# oled.net
KiCad netlist of a schematic drawn in Altium Designer
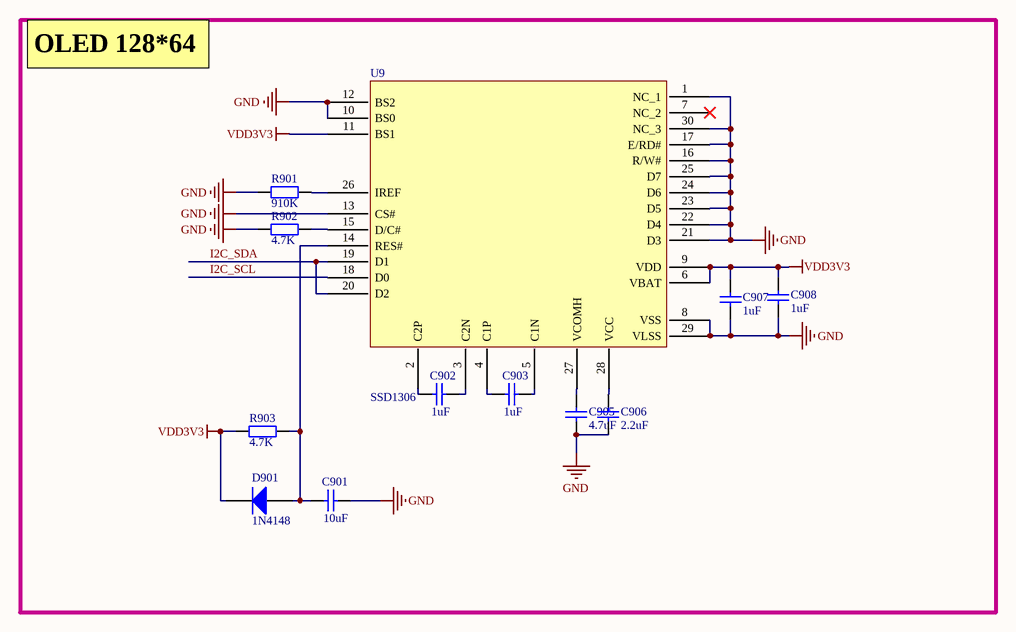
[diagram p0: oled.SchDoc]

(export (version "E")
  (design (tool "Eeschema 10.0.6"))
  (components
    (comp (ref "C901")
      (value "10uF")
      (footprint "0603_CAP")
      (description "Capacitor 0603")
      (fields (field (name "PUBLISHER") "Altium Limited"))
      (libsource (lib "Miscellaneous Devices") (part "Cap"))
    )
    (comp (ref "C902")
      (value "1uF")
      (footprint "0603_CAP")
      (description "Capacitor 0603")
      (fields (field (name "PUBLISHER") "Altium Limited"))
      (libsource (lib "Miscellaneous Devices") (part "Cap"))
    )
    (comp (ref "C903")
      (value "1uF")
      (footprint "0603_CAP")
      (description "Capacitor 0603")
      (fields (field (name "PUBLISHER") "Altium Limited"))
      (libsource (lib "Miscellaneous Devices") (part "Cap"))
    )
    (comp (ref "C905")
      (value "4.7uF")
      (footprint "0603_CAP")
      (description "Capacitor 0603")
      (fields (field (name "PUBLISHER") "Altium Limited"))
      (libsource (lib "Miscellaneous Devices") (part "Cap"))
    )
    (comp (ref "C906")
      (value "2.2uF")
      (footprint "0603_CAP")
      (description "Capacitor 0603")
      (fields (field (name "PUBLISHER") "Altium Limited"))
      (libsource (lib "Miscellaneous Devices") (part "Cap"))
    )
    (comp (ref "C907")
      (value "1uF")
      (footprint "0603_CAP")
      (description "Capacitor 0603")
      (fields (field (name "PUBLISHER") "Altium Limited"))
      (libsource (lib "Miscellaneous Devices") (part "Cap"))
    )
    (comp (ref "C908")
      (value "1uF")
      (footprint "0603_CAP")
      (description "Capacitor 0603")
      (fields (field (name "PUBLISHER") "Altium Limited"))
      (libsource (lib "Miscellaneous Devices") (part "Cap"))
    )
    (comp (ref "D901")
      (value "1N4148")
      (footprint "SOD-323")
      (description "IN4148 0805 SOD323")
      (fields (field (name "PUBLISHER") "Altium Limited"))
      (libsource (lib "Miscellaneous Devices") (part "Diode"))
    )
    (comp (ref "R901")
      (value "910K")
      (footprint "0603_CAP")
      (description "Resistor 0603")
      (fields (field (name "PUBLISHER") "Altium Limited"))
      (libsource (lib "Miscellaneous Devices") (part "Res2"))
    )
    (comp (ref "R902")
      (value "4.7K")
      (footprint "0603_CAP")
      (description "Resistor 0603")
      (fields (field (name "PUBLISHER") "Altium Limited"))
      (libsource (lib "Miscellaneous Devices") (part "Res2"))
    )
    (comp (ref "R903")
      (value "4.7K")
      (footprint "0603_CAP")
      (description "Resistor 0603")
      (fields (field (name "PUBLISHER") "Altium Limited"))
      (libsource (lib "Miscellaneous Devices") (part "Res2"))
    )
    (comp (ref "U9") (value "SSD1306") (footprint "SSD1306") (libsource (lib "Hardware") (part "SSD1306")))
  )
  (nets
    (net (code "1") (name "/I2C_SCL") (class "Default")
      (node (ref "U9") (pin "18") (pinfunction "D0_18") (pintype "passive"))
    )
    (net (code "2") (name "/I2C_SDA") (class "Default")
      (node (ref "U9") (pin "19") (pinfunction "D1_19") (pintype "passive"))
      (node (ref "U9") (pin "20") (pinfunction "D2_20") (pintype "passive"))
    )
    (net (code "3") (name "GND") (class "Default")
      (node (ref "C901") (pin "2") (pinfunction "2_2") (pintype "passive"))
      (node (ref "C905") (pin "1") (pinfunction "1_1") (pintype "passive"))
      (node (ref "C906") (pin "1") (pinfunction "1_1") (pintype "passive"))
      (node (ref "C907") (pin "1") (pinfunction "1_1") (pintype "passive"))
      (node (ref "C908") (pin "1") (pinfunction "1_1") (pintype "passive"))
      (node (ref "R901") (pin "2") (pinfunction "2_2") (pintype "passive"))
      (node (ref "R902") (pin "2") (pinfunction "2_2") (pintype "passive"))
      (node (ref "U9") (pin "1") (pinfunction "NC_1_1") (pintype "passive"))
      (node (ref "U9") (pin "10") (pinfunction "BS0_10") (pintype "passive"))
      (node (ref "U9") (pin "12") (pinfunction "BS2_12") (pintype "passive"))
      (node (ref "U9") (pin "13") (pinfunction "CS#_13") (pintype "passive"))
      (node (ref "U9") (pin "16") (pinfunction "R/W#_16") (pintype "passive"))
      (node (ref "U9") (pin "17") (pinfunction "E/RD#_17") (pintype "passive"))
      (node (ref "U9") (pin "21") (pinfunction "D3_21") (pintype "passive"))
      (node (ref "U9") (pin "22") (pinfunction "D4_22") (pintype "passive"))
      (node (ref "U9") (pin "23") (pinfunction "D5_23") (pintype "passive"))
      (node (ref "U9") (pin "24") (pinfunction "D6_24") (pintype "passive"))
      (node (ref "U9") (pin "25") (pinfunction "D7_25") (pintype "passive"))
      (node (ref "U9") (pin "29") (pinfunction "VLSS_29") (pintype "passive"))
      (node (ref "U9") (pin "30") (pinfunction "NC_3_30") (pintype "passive"))
      (node (ref "U9") (pin "8") (pinfunction "VSS_8") (pintype "passive"))
    )
    (net (code "4") (name "Net-(D901-A)") (class "Default")
      (node (ref "C901") (pin "1") (pinfunction "1_1") (pintype "passive"))
      (node (ref "D901") (pin "1") (pinfunction "A_1") (pintype "passive"))
      (node (ref "R903") (pin "1") (pinfunction "1_1") (pintype "passive"))
      (node (ref "U9") (pin "14") (pinfunction "RES#_14") (pintype "passive"))
    )
    (net (code "5") (name "Net-(U9-C1N)") (class "Default")
      (node (ref "C903") (pin "2") (pinfunction "2_2") (pintype "passive"))
      (node (ref "U9") (pin "5") (pinfunction "C1N_5") (pintype "passive"))
    )
    (net (code "6") (name "Net-(U9-C1P)") (class "Default")
      (node (ref "C903") (pin "1") (pinfunction "1_1") (pintype "passive"))
      (node (ref "U9") (pin "4") (pinfunction "C1P_4") (pintype "passive"))
    )
    (net (code "7") (name "Net-(U9-C2N)") (class "Default")
      (node (ref "C902") (pin "2") (pinfunction "2_2") (pintype "passive"))
      (node (ref "U9") (pin "3") (pinfunction "C2N_3") (pintype "passive"))
    )
    (net (code "8") (name "Net-(U9-C2P)") (class "Default")
      (node (ref "C902") (pin "1") (pinfunction "1_1") (pintype "passive"))
      (node (ref "U9") (pin "2") (pinfunction "C2P_2") (pintype "passive"))
    )
    (net (code "9") (name "Net-(U9-D{slash}C#)") (class "Default")
      (node (ref "R902") (pin "1") (pinfunction "1_1") (pintype "passive"))
      (node (ref "U9") (pin "15") (pinfunction "D/C#_15") (pintype "passive"))
    )
    (net (code "10") (name "Net-(U9-IREF)") (class "Default")
      (node (ref "R901") (pin "1") (pinfunction "1_1") (pintype "passive"))
      (node (ref "U9") (pin "26") (pinfunction "IREF_26") (pintype "passive"))
    )
    (net (code "11") (name "Net-(U9-VCC)") (class "Default")
      (node (ref "C906") (pin "2") (pinfunction "2_2") (pintype "passive"))
      (node (ref "U9") (pin "28") (pinfunction "VCC_28") (pintype "passive"))
    )
    (net (code "12") (name "Net-(U9-VCOMH)") (class "Default")
      (node (ref "C905") (pin "2") (pinfunction "2_2") (pintype "passive"))
      (node (ref "U9") (pin "27") (pinfunction "VCOMH_27") (pintype "passive"))
    )
    (net (code "13") (name "VDD3V3") (class "Default")
      (node (ref "C907") (pin "2") (pinfunction "2_2") (pintype "passive"))
      (node (ref "C908") (pin "2") (pinfunction "2_2") (pintype "passive"))
      (node (ref "D901") (pin "2") (pinfunction "K_2") (pintype "passive"))
      (node (ref "R903") (pin "2") (pinfunction "2_2") (pintype "passive"))
      (node (ref "U9") (pin "11") (pinfunction "BS1_11") (pintype "passive"))
      (node (ref "U9") (pin "6") (pinfunction "VBAT_6") (pintype "passive"))
      (node (ref "U9") (pin "9") (pinfunction "VDD_9") (pintype "passive"))
    )
    (net (code "14") (name "unconnected-(U9-NC_2-Pad7)") (class "Default")
      (node (ref "U9") (pin "7") (pinfunction "NC_2_7") (pintype "passive+no_connect"))
    )
  )
)
